# MCU.net
KiCad netlist of a schematic drawn in Altium Designer
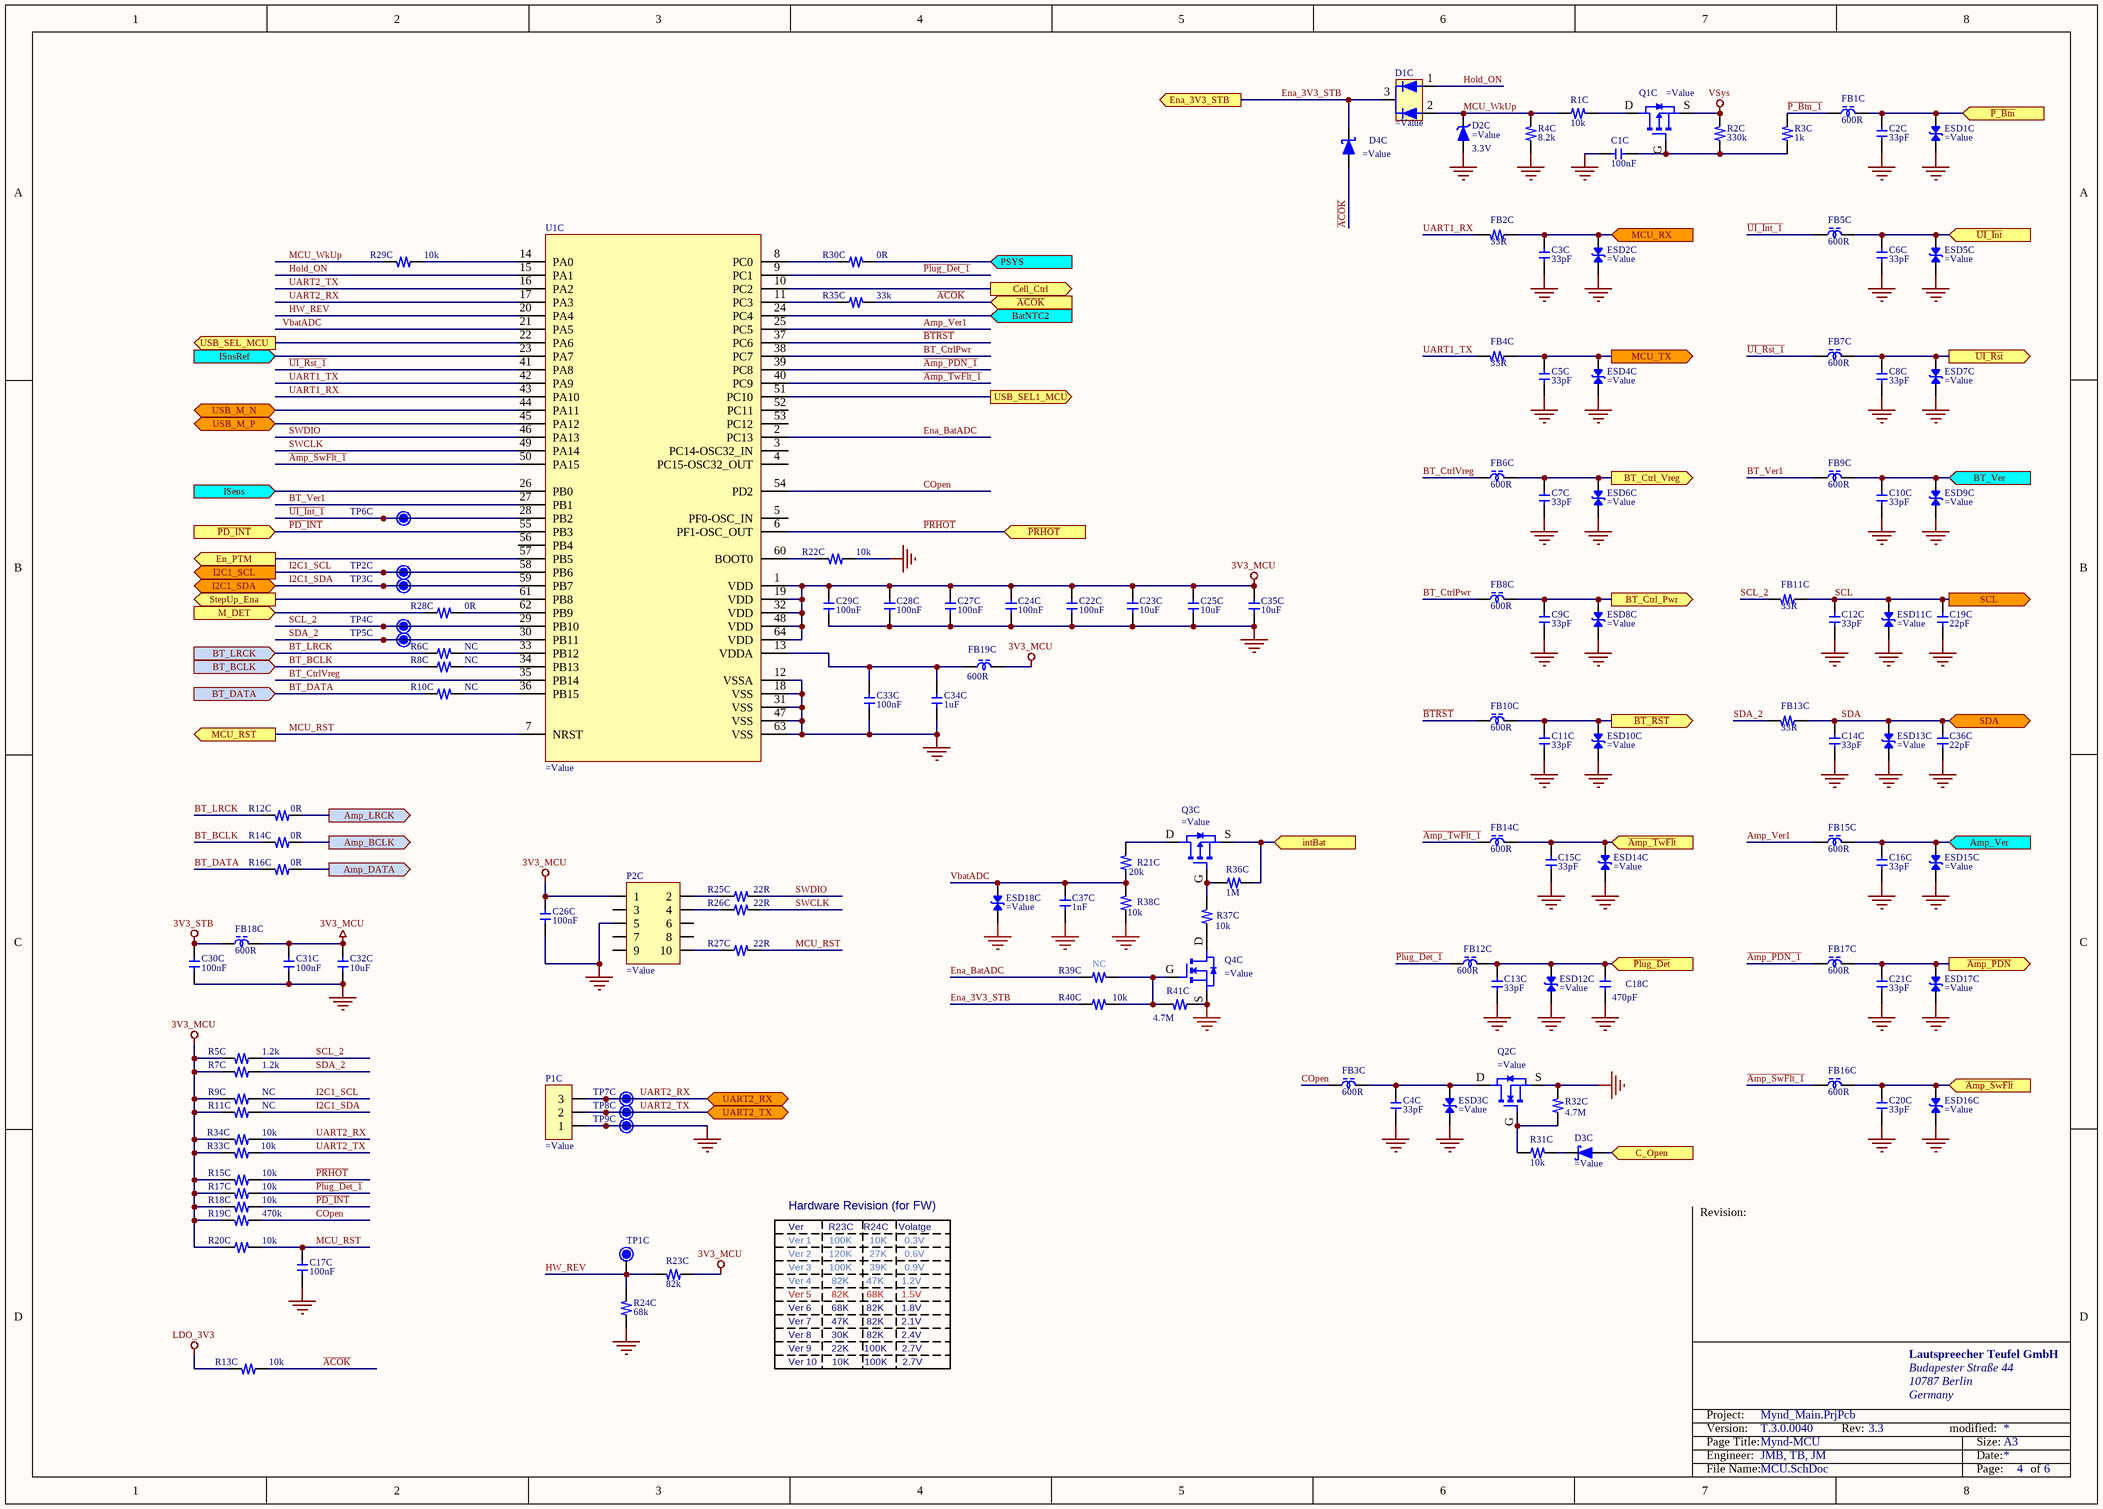
[diagram p0: MCU.SchDoc]

(export (version "E")
  (design (tool "Eeschema 10.0.6"))
  (components
    (comp (ref "C1C")
      (value "100nF")
      (footprint "C0603X100")
      (description "PSHF SMD M CAP 100nF 50V ±10% 0603 X7R")
      (fields (field (name "MANUFACTURER") "Multi Sourced") (field (name "TOLERANCE") "±10%"))
      (libsource (lib "altium-import") (part "root_0_mirrored_CAP1_"))
    )
    (comp (ref "C2C")
      (value "33pF")
      (footprint "C0603X80")
      (description "PSHF SMD M CAP 33pF 50V ±5% 0603 NPO")
      (fields (field (name "MANUFACTURER") "Multi Sourced") (field (name "TOLERANCE") "±5%"))
      (libsource (lib "altium-import") (part "root_3_mirrored_CAP1_"))
    )
    (comp (ref "C3C")
      (value "33pF")
      (footprint "C0603X80")
      (description "PSHF SMD M CAP 33pF 50V ±5% 0603 NPO")
      (fields (field (name "MANUFACTURER") "Multi Sourced") (field (name "TOLERANCE") "±5%"))
      (libsource (lib "altium-import") (part "root_3_mirrored_CAP1_"))
    )
    (comp (ref "C4C")
      (value "33pF")
      (footprint "C0603X80")
      (description "PSHF SMD M CAP 33pF 50V ±5% 0603 NPO")
      (fields (field (name "MANUFACTURER") "Multi Sourced") (field (name "TOLERANCE") "±5%"))
      (libsource (lib "altium-import") (part "root_3_mirrored_CAP1_"))
    )
    (comp (ref "C5C")
      (value "33pF")
      (footprint "C0603X80")
      (description "PSHF SMD M CAP 33pF 50V ±5% 0603 NPO")
      (fields (field (name "MANUFACTURER") "Multi Sourced") (field (name "TOLERANCE") "±5%"))
      (libsource (lib "altium-import") (part "root_3_mirrored_CAP1_"))
    )
    (comp (ref "C6C")
      (value "33pF")
      (footprint "C0603X80")
      (description "PSHF SMD M CAP 33pF 50V ±5% 0603 NPO")
      (fields (field (name "MANUFACTURER") "Multi Sourced") (field (name "TOLERANCE") "±5%"))
      (libsource (lib "altium-import") (part "root_3_mirrored_CAP1_"))
    )
    (comp (ref "C7C")
      (value "33pF")
      (footprint "C0603X80")
      (description "PSHF SMD M CAP 33pF 50V ±5% 0603 NPO")
      (fields (field (name "MANUFACTURER") "Multi Sourced") (field (name "TOLERANCE") "±5%"))
      (libsource (lib "altium-import") (part "root_3_mirrored_CAP1_"))
    )
    (comp (ref "C8C")
      (value "33pF")
      (footprint "C0603X80")
      (description "PSHF SMD M CAP 33pF 50V ±5% 0603 NPO")
      (fields (field (name "MANUFACTURER") "Multi Sourced") (field (name "TOLERANCE") "±5%"))
      (libsource (lib "altium-import") (part "root_3_mirrored_CAP1_"))
    )
    (comp (ref "C9C")
      (value "33pF")
      (footprint "C0603X80")
      (description "PSHF SMD M CAP 33pF 50V ±5% 0603 NPO")
      (fields (field (name "MANUFACTURER") "Multi Sourced") (field (name "TOLERANCE") "±5%"))
      (libsource (lib "altium-import") (part "root_3_mirrored_CAP1_"))
    )
    (comp (ref "C10C")
      (value "33pF")
      (footprint "C0603X80")
      (description "PSHF SMD M CAP 33pF 50V ±5% 0603 NPO")
      (fields (field (name "MANUFACTURER") "Multi Sourced") (field (name "TOLERANCE") "±5%"))
      (libsource (lib "altium-import") (part "root_3_mirrored_CAP1_"))
    )
    (comp (ref "C11C")
      (value "33pF")
      (footprint "C0603X80")
      (description "PSHF SMD M CAP 33pF 50V ±5% 0603 NPO")
      (fields (field (name "MANUFACTURER") "Multi Sourced") (field (name "TOLERANCE") "±5%"))
      (libsource (lib "altium-import") (part "root_3_mirrored_CAP1_"))
    )
    (comp (ref "C12C")
      (value "33pF")
      (footprint "C0603X80")
      (description "PSHF SMD M CAP 33pF 50V ±5% 0603 NPO")
      (fields (field (name "MANUFACTURER") "Multi Sourced") (field (name "TOLERANCE") "±5%"))
      (libsource (lib "altium-import") (part "root_3_mirrored_CAP1_"))
    )
    (comp (ref "C13C")
      (value "33pF")
      (footprint "C0603X80")
      (description "PSHF SMD M CAP 33pF 50V ±5% 0603 NPO")
      (fields (field (name "MANUFACTURER") "Multi Sourced") (field (name "TOLERANCE") "±5%"))
      (libsource (lib "altium-import") (part "root_3_mirrored_CAP1_"))
    )
    (comp (ref "C14C")
      (value "33pF")
      (footprint "C0603X80")
      (description "PSHF SMD M CAP 33pF 50V ±5% 0603 NPO")
      (fields (field (name "MANUFACTURER") "Multi Sourced") (field (name "TOLERANCE") "±5%"))
      (libsource (lib "altium-import") (part "root_3_mirrored_CAP1_"))
    )
    (comp (ref "C15C")
      (value "33pF")
      (footprint "C0603X80")
      (description "PSHF SMD M CAP 33pF 50V ±5% 0603 NPO")
      (fields (field (name "MANUFACTURER") "Multi Sourced") (field (name "TOLERANCE") "±5%"))
      (libsource (lib "altium-import") (part "root_3_mirrored_CAP1_"))
    )
    (comp (ref "C16C")
      (value "33pF")
      (footprint "C0603X80")
      (description "PSHF SMD M CAP 33pF 50V ±5% 0603 NPO")
      (fields (field (name "MANUFACTURER") "Multi Sourced") (field (name "TOLERANCE") "±5%"))
      (libsource (lib "altium-import") (part "root_3_mirrored_CAP1_"))
    )
    (comp (ref "C17C")
      (value "100nF")
      (footprint "C0603X100")
      (description "PSHF SMD M CAP 100nF 50V ±10% 0603 X7R")
      (fields (field (name "MANUFACTURER") "Multi Sourced") (field (name "TOLERANCE") "±10%"))
      (libsource (lib "altium-import") (part "root_3_CAP1_"))
    )
    (comp (ref "C18C")
      (value "470pF")
      (footprint "C0603X80")
      (description "GPHF SMD CAP 470pF 50V 10%")
      (fields (field (name "MANUFACTURER") "Multi Sourced") (field (name "TOLERANCE") "±10%"))
      (libsource (lib "altium-import") (part "root_3_CAP1_"))
    )
    (comp (ref "C19C")
      (value "22pF")
      (footprint "C0603X80")
      (description "GPHF SMD M CAP 22pF 50V ±5% 0603 NPO")
      (fields (field (name "MANUFACTURER") "Multi Sourced") (field (name "TOLERANCE") "±5%"))
      (libsource (lib "altium-import") (part "root_3_mirrored_CAP1_"))
    )
    (comp (ref "C20C")
      (value "33pF")
      (footprint "C0603X80")
      (description "PSHF SMD M CAP 33pF 50V ±5% 0603 NPO")
      (fields (field (name "MANUFACTURER") "Multi Sourced") (field (name "TOLERANCE") "±5%"))
      (libsource (lib "altium-import") (part "root_3_mirrored_CAP1_"))
    )
    (comp (ref "C21C")
      (value "33pF")
      (footprint "C0603X80")
      (description "PSHF SMD M CAP 33pF 50V ±5% 0603 NPO")
      (fields (field (name "MANUFACTURER") "Multi Sourced") (field (name "TOLERANCE") "±5%"))
      (libsource (lib "altium-import") (part "root_3_mirrored_CAP1_"))
    )
    (comp (ref "C22C")
      (value "100nF")
      (footprint "C0603X100")
      (description "PSHF SMD M CAP 100nF 50V ±10% 0603 X7R")
      (fields (field (name "MANUFACTURER") "Multi Sourced") (field (name "TOLERANCE") "±10%"))
      (libsource (lib "altium-import") (part "root_3_CAP1_"))
    )
    (comp (ref "C23C")
      (value "10uF")
      (footprint "C0805_145")
      (description "PSHF SMD M CAP 10uF 16V ±10% 0805 X7R")
      (fields (field (name "MANUFACTURER") "Multi Sourced") (field (name "TOLERANCE") "±10%"))
      (libsource (lib "altium-import") (part "root_3_CAP1_"))
    )
    (comp (ref "C24C")
      (value "100nF")
      (footprint "C0603X100")
      (description "PSHF SMD M CAP 100nF 50V ±10% 0603 X7R")
      (fields (field (name "MANUFACTURER") "Multi Sourced") (field (name "TOLERANCE") "±10%"))
      (libsource (lib "altium-import") (part "root_3_CAP1_"))
    )
    (comp (ref "C25C")
      (value "10uF")
      (footprint "C0805_145")
      (description "PSHF SMD M CAP 10uF 16V ±10% 0805 X7R")
      (fields (field (name "MANUFACTURER") "Multi Sourced") (field (name "TOLERANCE") "±10%"))
      (libsource (lib "altium-import") (part "root_3_CAP1_"))
    )
    (comp (ref "C26C")
      (value "100nF")
      (footprint "C0603X100")
      (description "PSHF SMD M CAP 100nF 50V ±10% 0603 X7R")
      (fields (field (name "MANUFACTURER") "Multi Sourced") (field (name "TOLERANCE") "±10%"))
      (libsource (lib "altium-import") (part "root_3_CAP1_"))
    )
    (comp (ref "C27C")
      (value "100nF")
      (footprint "C0603X100")
      (description "PSHF SMD M CAP 100nF 50V ±10% 0603 X7R")
      (fields (field (name "MANUFACTURER") "Multi Sourced") (field (name "TOLERANCE") "±10%"))
      (libsource (lib "altium-import") (part "root_3_CAP1_"))
    )
    (comp (ref "C28C")
      (value "100nF")
      (footprint "C0603X100")
      (description "PSHF SMD M CAP 100nF 50V ±10% 0603 X7R")
      (fields (field (name "MANUFACTURER") "Multi Sourced") (field (name "TOLERANCE") "±10%"))
      (libsource (lib "altium-import") (part "root_3_CAP1_"))
    )
    (comp (ref "C29C")
      (value "100nF")
      (footprint "C0603X100")
      (description "PSHF SMD M CAP 100nF 50V ±10% 0603 X7R")
      (fields (field (name "MANUFACTURER") "Multi Sourced") (field (name "TOLERANCE") "±10%"))
      (libsource (lib "altium-import") (part "root_3_CAP1_"))
    )
    (comp (ref "C30C")
      (value "100nF")
      (footprint "C0603X100")
      (description "PSHF SMD M CAP 100nF 50V ±10% 0603 X7R")
      (fields (field (name "MANUFACTURER") "Multi Sourced") (field (name "TOLERANCE") "±10%"))
      (libsource (lib "altium-import") (part "root_3_CAP1_"))
    )
    (comp (ref "C31C")
      (value "100nF")
      (footprint "C0603X100")
      (description "PSHF SMD M CAP 100nF 50V ±10% 0603 X7R")
      (fields (field (name "MANUFACTURER") "Multi Sourced") (field (name "TOLERANCE") "±10%"))
      (libsource (lib "altium-import") (part "root_3_CAP1_"))
    )
    (comp (ref "C32C")
      (value "10uF")
      (footprint "C0805_145")
      (description "PSHF SMD M CAP 10uF 16V ±10% 0805 X7R")
      (fields (field (name "MANUFACTURER") "Multi Sourced") (field (name "TOLERANCE") "±10%"))
      (libsource (lib "altium-import") (part "root_3_CAP1_"))
    )
    (comp (ref "C33C")
      (value "100nF")
      (footprint "C0603X100")
      (description "PSHF SMD M CAP 100nF 50V ±10% 0603 X7R")
      (fields (field (name "MANUFACTURER") "Multi Sourced") (field (name "TOLERANCE") "±10%"))
      (libsource (lib "altium-import") (part "root_3_CAP1_"))
    )
    (comp (ref "C34C")
      (value "1uF")
      (footprint "C0603X105")
      (description "PSHF SMD M CAP 1uF 16V ±10% 0603 X7R")
      (fields (field (name "MANUFACTURER") "Multi Sourced") (field (name "TOLERANCE") "±10%"))
      (libsource (lib "altium-import") (part "root_3_CAP1_"))
    )
    (comp (ref "C35C")
      (value "10uF")
      (footprint "C0805_145")
      (description "PSHF SMD M CAP 10uF 16V ±10% 0805 X7R")
      (fields (field (name "MANUFACTURER") "Multi Sourced") (field (name "TOLERANCE") "±10%"))
      (libsource (lib "altium-import") (part "root_1_CAP1_"))
    )
    (comp (ref "C36C")
      (value "22pF")
      (footprint "C0603X80")
      (description "GPHF SMD M CAP 22pF 50V ±5% 0603 NPO")
      (fields (field (name "MANUFACTURER") "Multi Sourced") (field (name "TOLERANCE") "±5%"))
      (libsource (lib "altium-import") (part "root_3_mirrored_CAP1_"))
    )
    (comp (ref "C37C")
      (value "1nF")
      (footprint "C0603X100")
      (description "GPHF SMD M CAP 1nF 50V ±10% 0603 X7R")
      (fields (field (name "MANUFACTURER") "Multi Sourced") (field (name "TOLERANCE") "±10%"))
      (libsource (lib "altium-import") (part "root_3_CAP1_"))
    )
    (comp (ref "D1C")
      (value "~")
      (footprint "SOT23-123")
      (description "PS SMD DIODE 3P 30V SOT-23 BAT54C CJ")
      (fields (field (name "MANUFACTURER") "[CJ]") (field (name "VOLTAGE") "30V"))
      (libsource (lib "altium-import") (part "root_3_mirrored_DIODE_SWITCHING4_"))
    )
    (comp (ref "D2C")
      (value "~")
      (footprint "SOD-123")
      (description "GP SMD ZENER 3.3V 0.5W SOD-123 CJ")
      (fields
        (field (name "MANUFACTURER") "[CJ]")
        (field (name "VOLTAGE") "3.3V")
        (field (name "PART_NUMBER") "BZT52C3V3")
      )
      (libsource (lib "altium-import") (part "root_1_mirrored_DIODE_ZENER1_"))
    )
    (comp (ref "D3C")
      (value "~")
      (footprint "SOD-323")
      (description "GP SMD DIODE 2P 30V SOD323 BAT54WS PANJIT")
      (fields (field (name "MANUFACTURER") "PANJIT") (field (name "VOLTAGE") "30V"))
      (libsource (lib "altium-import") (part "root_2_DIODE_SCHOTTKY1_"))
    )
    (comp (ref "D4C")
      (value "~")
      (footprint "SOD-323")
      (description "GP SMD DIODE 2P 30V SOD323 BAT54WS PANJIT")
      (fields (field (name "MANUFACTURER") "PANJIT") (field (name "VOLTAGE") "30V"))
      (libsource (lib "altium-import") (part "root_1_mirrored_DIODE_SCHOTTKY1_"))
    )
    (comp (ref "ESD1C")
      (value "~")
      (footprint "DFN2_100X60X50_65")
      (description "SMD TVS 2P DFN1006 BDFN2C121V")
      (fields (field (name "MANUFACTURER") "[]") (field (name "PART_NUMBER") "BDFN2C121V"))
      (libsource (lib "altium-import") (part "root_3_DIODE_BID_ESD2_"))
    )
    (comp (ref "ESD2C")
      (value "~")
      (footprint "DFN2_100X60X50_65")
      (description "GP SMD TVS 2P DFN1006-2 AU3321P1 APM")
      (fields (field (name "MANUFACTURER") "APM") (field (name "VOLTAGE") "3.3V"))
      (libsource (lib "altium-import") (part "root_1_DIODE_BID_ESD2_"))
    )
    (comp (ref "ESD3C")
      (value "~")
      (footprint "DFN2_100X60X50_65")
      (description "GP SMD TVS 2P DFN1006-2 AU3321P1 APM")
      (fields (field (name "MANUFACTURER") "APM") (field (name "VOLTAGE") "3.3V"))
      (libsource (lib "altium-import") (part "root_1_DIODE_BID_ESD2_"))
    )
    (comp (ref "ESD4C")
      (value "~")
      (footprint "DFN2_100X60X50_65")
      (description "GP SMD TVS 2P DFN1006-2 AU3321P1 APM")
      (fields (field (name "MANUFACTURER") "APM") (field (name "VOLTAGE") "3.3V"))
      (libsource (lib "altium-import") (part "root_1_DIODE_BID_ESD2_"))
    )
    (comp (ref "ESD5C")
      (value "~")
      (footprint "DFN2_100X60X50_65")
      (description "GP SMD TVS 2P DFN1006-2 AU3321P1 APM")
      (fields (field (name "MANUFACTURER") "APM") (field (name "VOLTAGE") "3.3V"))
      (libsource (lib "altium-import") (part "root_1_DIODE_BID_ESD2_"))
    )
    (comp (ref "ESD6C")
      (value "~")
      (footprint "DFN2_100X60X50_65")
      (description "GP SMD TVS 2P DFN1006-2 AU3321P1 APM")
      (fields (field (name "MANUFACTURER") "APM") (field (name "VOLTAGE") "3.3V"))
      (libsource (lib "altium-import") (part "root_1_DIODE_BID_ESD2_"))
    )
    (comp (ref "ESD7C")
      (value "~")
      (footprint "DFN2_100X60X50_65")
      (description "GP SMD TVS 2P DFN1006-2 AU3321P1 APM")
      (fields (field (name "MANUFACTURER") "APM") (field (name "VOLTAGE") "3.3V"))
      (libsource (lib "altium-import") (part "root_1_DIODE_BID_ESD2_"))
    )
    (comp (ref "ESD8C")
      (value "~")
      (footprint "DFN2_100X60X50_65")
      (description "GP SMD TVS 2P DFN1006-2 AU3321P1 APM")
      (fields (field (name "MANUFACTURER") "APM") (field (name "VOLTAGE") "3.3V"))
      (libsource (lib "altium-import") (part "root_1_DIODE_BID_ESD2_"))
    )
    (comp (ref "ESD9C")
      (value "~")
      (footprint "DFN2_100X60X50_65")
      (description "GP SMD TVS 2P DFN1006-2 AU3321P1 APM")
      (fields (field (name "MANUFACTURER") "APM") (field (name "VOLTAGE") "3.3V"))
      (libsource (lib "altium-import") (part "root_1_DIODE_BID_ESD2_"))
    )
    (comp (ref "ESD10C")
      (value "~")
      (footprint "DFN2_100X60X50_65")
      (description "GP SMD TVS 2P DFN1006-2 AU3321P1 APM")
      (fields (field (name "MANUFACTURER") "APM") (field (name "VOLTAGE") "3.3V"))
      (libsource (lib "altium-import") (part "root_1_DIODE_BID_ESD2_"))
    )
    (comp (ref "ESD11C")
      (value "~")
      (footprint "DFN2_100X60X50_65")
      (description "GP SMD TVS 2P DFN1006-2 AU3321P1 APM")
      (fields (field (name "MANUFACTURER") "APM") (field (name "VOLTAGE") "3.3V"))
      (libsource (lib "altium-import") (part "root_1_DIODE_BID_ESD2_"))
    )
    (comp (ref "ESD12C")
      (value "~")
      (footprint "DFN2_100X60X50_65")
      (description "GP SMD TVS 2P DFN1006-2 AU3321P1 APM")
      (fields (field (name "MANUFACTURER") "APM") (field (name "VOLTAGE") "3.3V"))
      (libsource (lib "altium-import") (part "root_1_DIODE_BID_ESD2_"))
    )
    (comp (ref "ESD13C")
      (value "~")
      (footprint "DFN2_100X60X50_65")
      (description "GP SMD TVS 2P DFN1006-2 AU3321P1 APM")
      (fields (field (name "MANUFACTURER") "APM") (field (name "VOLTAGE") "3.3V"))
      (libsource (lib "altium-import") (part "root_1_DIODE_BID_ESD2_"))
    )
    (comp (ref "ESD14C")
      (value "~")
      (footprint "DFN2_100X60X50_65")
      (description "GP SMD TVS 2P DFN1006-2 AU3321P1 APM")
      (fields (field (name "MANUFACTURER") "APM") (field (name "VOLTAGE") "3.3V"))
      (libsource (lib "altium-import") (part "root_1_DIODE_BID_ESD2_"))
    )
    (comp (ref "ESD15C")
      (value "~")
      (footprint "DFN2_100X60X50_65")
      (description "GP SMD TVS 2P DFN1006-2 AU3321P1 APM")
      (fields (field (name "MANUFACTURER") "APM") (field (name "VOLTAGE") "3.3V"))
      (libsource (lib "altium-import") (part "root_1_DIODE_BID_ESD2_"))
    )
    (comp (ref "ESD16C")
      (value "~")
      (footprint "DFN2_100X60X50_65")
      (description "GP SMD TVS 2P DFN1006-2 AU3321P1 APM")
      (fields (field (name "MANUFACTURER") "APM") (field (name "VOLTAGE") "3.3V"))
      (libsource (lib "altium-import") (part "root_1_DIODE_BID_ESD2_"))
    )
    (comp (ref "ESD17C")
      (value "~")
      (footprint "DFN2_100X60X50_65")
      (description "GP SMD TVS 2P DFN1006-2 AU3321P1 APM")
      (fields (field (name "MANUFACTURER") "APM") (field (name "VOLTAGE") "3.3V"))
      (libsource (lib "altium-import") (part "root_1_DIODE_BID_ESD2_"))
    )
    (comp (ref "ESD18C")
      (value "~")
      (footprint "DFN2_100X60X50_65")
      (description "GP SMD TVS 2P DFN1006-2 AU3321P1 APM")
      (fields (field (name "MANUFACTURER") "APM") (field (name "VOLTAGE") "3.3V"))
      (libsource (lib "altium-import") (part "root_1_DIODE_BID_ESD2_"))
    )
    (comp (ref "FB1C")
      (value "600R")
      (footprint "L0603")
      (description "PSHF SMD FERRITE BEAD 600OHM 25% 0603")
      (fields (field (name "MANUFACTURER") "TSA") (field (name "TOLERANCE") "1:25%"))
      (libsource (lib "altium-import") (part "root_0_Bead1_"))
    )
    (comp (ref "FB2C")
      (value "33R")
      (footprint "R0603")
      (description "GPHF SMD RES. 33OHM 1/10W 5% 0603")
      (fields (field (name "MANUFACTURER") "Multi-Sourced") (field (name "TOLERANCE") "5%"))
      (libsource (lib "altium-import") (part "root_0_RES1_"))
    )
    (comp (ref "FB3C")
      (value "600R")
      (footprint "L0603")
      (description "PSHF SMD FERRITE BEAD 600OHM 25% 0603")
      (fields (field (name "MANUFACTURER") "TSA") (field (name "TOLERANCE") "1:25%"))
      (libsource (lib "altium-import") (part "root_0_Bead1_"))
    )
    (comp (ref "FB4C")
      (value "33R")
      (footprint "R0603")
      (description "GPHF SMD RES. 33OHM 1/10W 5% 0603")
      (fields (field (name "MANUFACTURER") "Multi-Sourced") (field (name "TOLERANCE") "5%"))
      (libsource (lib "altium-import") (part "root_0_RES1_"))
    )
    (comp (ref "FB5C")
      (value "600R")
      (footprint "L0603")
      (description "PSHF SMD FERRITE BEAD 600OHM 25% 0603")
      (fields (field (name "MANUFACTURER") "TSA") (field (name "TOLERANCE") "1:25%"))
      (libsource (lib "altium-import") (part "root_0_Bead1_"))
    )
    (comp (ref "FB6C")
      (value "600R")
      (footprint "L0603")
      (description "PSHF SMD FERRITE BEAD 600OHM 25% 0603")
      (fields (field (name "MANUFACTURER") "TSA") (field (name "TOLERANCE") "1:25%"))
      (libsource (lib "altium-import") (part "root_0_Bead1_"))
    )
    (comp (ref "FB7C")
      (value "600R")
      (footprint "L0603")
      (description "PSHF SMD FERRITE BEAD 600OHM 25% 0603")
      (fields (field (name "MANUFACTURER") "TSA") (field (name "TOLERANCE") "1:25%"))
      (libsource (lib "altium-import") (part "root_0_Bead1_"))
    )
    (comp (ref "FB8C")
      (value "600R")
      (footprint "L0603")
      (description "PSHF SMD FERRITE BEAD 600OHM 25% 0603")
      (fields (field (name "MANUFACTURER") "TSA") (field (name "TOLERANCE") "1:25%"))
      (libsource (lib "altium-import") (part "root_0_Bead1_"))
    )
    (comp (ref "FB9C")
      (value "600R")
      (footprint "L0603")
      (description "PSHF SMD FERRITE BEAD 600OHM 25% 0603")
      (fields (field (name "MANUFACTURER") "TSA") (field (name "TOLERANCE") "1:25%"))
      (libsource (lib "altium-import") (part "root_0_Bead1_"))
    )
    (comp (ref "FB10C")
      (value "600R")
      (footprint "L0603")
      (description "PSHF SMD FERRITE BEAD 600OHM 25% 0603")
      (fields (field (name "MANUFACTURER") "TSA") (field (name "TOLERANCE") "1:25%"))
      (libsource (lib "altium-import") (part "root_0_Bead1_"))
    )
    (comp (ref "FB11C")
      (value "33R")
      (footprint "R0603")
      (description "GPHF SMD RES. 33OHM 1/10W 5% 0603")
      (fields (field (name "MANUFACTURER") "Multi-Sourced") (field (name "TOLERANCE") "5%"))
      (libsource (lib "altium-import") (part "root_0_RES1_"))
    )
    (comp (ref "FB12C")
      (value "600R")
      (footprint "L0603")
      (description "PSHF SMD FERRITE BEAD 600OHM 25% 0603")
      (fields (field (name "MANUFACTURER") "TSA") (field (name "TOLERANCE") "1:25%"))
      (libsource (lib "altium-import") (part "root_0_Bead1_"))
    )
    (comp (ref "FB13C")
      (value "33R")
      (footprint "R0603")
      (description "GPHF SMD RES. 33OHM 1/10W 5% 0603")
      (fields (field (name "MANUFACTURER") "Multi-Sourced") (field (name "TOLERANCE") "5%"))
      (libsource (lib "altium-import") (part "root_0_RES1_"))
    )
    (comp (ref "FB14C")
      (value "600R")
      (footprint "L0603")
      (description "PSHF SMD FERRITE BEAD 600OHM 25% 0603")
      (fields (field (name "MANUFACTURER") "TSA") (field (name "TOLERANCE") "1:25%"))
      (libsource (lib "altium-import") (part "root_0_Bead1_"))
    )
    (comp (ref "FB15C")
      (value "600R")
      (footprint "L0603")
      (description "PSHF SMD FERRITE BEAD 600OHM 25% 0603")
      (fields (field (name "MANUFACTURER") "TSA") (field (name "TOLERANCE") "1:25%"))
      (libsource (lib "altium-import") (part "root_0_Bead1_"))
    )
    (comp (ref "FB16C")
      (value "600R")
      (footprint "L0603")
      (description "PSHF SMD FERRITE BEAD 600OHM 25% 0603")
      (fields (field (name "MANUFACTURER") "TSA") (field (name "TOLERANCE") "1:25%"))
      (libsource (lib "altium-import") (part "root_0_Bead1_"))
    )
    (comp (ref "FB17C")
      (value "600R")
      (footprint "L0603")
      (description "PSHF SMD FERRITE BEAD 600OHM 25% 0603")
      (fields (field (name "MANUFACTURER") "TSA") (field (name "TOLERANCE") "1:25%"))
      (libsource (lib "altium-import") (part "root_0_Bead1_"))
    )
    (comp (ref "FB18C")
      (value "600R")
      (footprint "L0603")
      (description "PSHF SMD FERRITE BEAD 600OHM 25% 0603")
      (fields (field (name "MANUFACTURER") "TSA") (field (name "TOLERANCE") "1:25%"))
      (libsource (lib "altium-import") (part "root_0_Bead1_"))
    )
    (comp (ref "FB19C")
      (value "600R")
      (footprint "L0603")
      (description "PSHF SMD FERRITE BEAD 600OHM 25% 0603")
      (fields (field (name "MANUFACTURER") "TSA") (field (name "TOLERANCE") "1:25%"))
      (libsource (lib "altium-import") (part "root_0_Bead1_"))
    )
    (comp (ref "P1C")
      (value "~")
      (footprint "Pin_Header_SMD_S_T_254_3P")
      (description "GP HEADER PIN 3P P=2.54mm 90° GOLD")
      (fields (field (name "MANUFACTURER") "[null]") (field (name "PART_NUMBER") "3P PITCH=2.54mm"))
      (libsource (lib "altium-import") (part "root_2_mirrored_CON 3P_"))
    )
    (comp (ref "P2C")
      (value "~")
      (footprint "Pin_Header_2x5_127")
      (description "SMD BTB CONNECTOR 10P P1.27mm GOLD")
      (fields (field (name "MANUFACTURER") "MINGHENG") (field (name "PART_NUMBER") "1.27PH 2X5P H2.0 SMT"))
      (libsource (lib "altium-import") (part "root_0_CON 2X5P_"))
    )
    (comp (ref "Q1C")
      (value "~")
      (footprint "SOT23-GSD")
      (description "GS SMD FET 3P -30V SOT-23 CJ3401 CJ")
      (fields (field (name "MANUFACTURER") "[CJ]") (field (name "VOLTAGE") "-30"))
      (libsource (lib "altium-import") (part "root_1_P-MOS1_"))
    )
    (comp (ref "Q2C")
      (value "~")
      (footprint "SOT23-GSD")
      (description "GP SMD FET 3P SOT23 2N7002K CTE")
      (fields (field (name "MANUFACTURER") "CTE") (field (name "VOLTAGE") "60V"))
      (libsource (lib "altium-import") (part "root_1_N-MOS1_"))
    )
    (comp (ref "Q3C")
      (value "~")
      (footprint "SOT23-GSD")
      (description "GS SMD FET 3P -30V SOT-23 CJ3401 CJ")
      (fields (field (name "MANUFACTURER") "[CJ]") (field (name "VOLTAGE") "-30"))
      (libsource (lib "altium-import") (part "root_1_P-MOS1_"))
    )
    (comp (ref "Q4C")
      (value "~")
      (footprint "SOT23-GSD")
      (description "GP SMD FET 3P SOT23 2N7002K CTE")
      (fields (field (name "MANUFACTURER") "CTE") (field (name "VOLTAGE") "60V"))
      (libsource (lib "altium-import") (part "root_0_N-MOS1_"))
    )
    (comp (ref "R1C")
      (value "10k")
      (footprint "R0603")
      (description "PS SMD RES. 10KOHM 1/10W 1% 0603")
      (fields (field (name "TOLERANCE") "1%") (field (name "MANUFACTURER") "Multi-Sourced"))
      (libsource (lib "altium-import") (part "root_2_mirrored_RES1_"))
    )
    (comp (ref "R2C")
      (value "330k")
      (footprint "R0603")
      (description "PS SMD RES. 330KOHM 1/10W 1% 0603")
      (fields (field (name "TOLERANCE") "1%") (field (name "MANUFACTURER") "Multi-Sourced"))
      (libsource (lib "altium-import") (part "root_1_mirrored_RES1_"))
    )
    (comp (ref "R3C")
      (value "1k")
      (footprint "R0603")
      (description "PS SMD RES. 1KOHM 1/10W 1% 0603")
      (fields (field (name "TOLERANCE") "1%") (field (name "MANUFACTURER") "Multi-Sourced"))
      (libsource (lib "altium-import") (part "root_1_mirrored_RES1_"))
    )
    (comp (ref "R4C")
      (value "8.2k")
      (footprint "R0603")
      (description "PS SMD RES. 8.2KOHM 1/10W 1% 0603")
      (fields (field (name "TOLERANCE") "1%") (field (name "MANUFACTURER") "Multi-Sourced"))
      (libsource (lib "altium-import") (part "root_1_mirrored_RES1_"))
    )
    (comp (ref "R5C")
      (value "1.2k")
      (footprint "R0603")
      (description "PS SMD RES. 1.2KOHM 1/10W 1% 0603")
      (fields (field (name "TOLERANCE") "1%") (field (name "MANUFACTURER") "Multi-Sourced"))
      (libsource (lib "altium-import") (part "root_0_RES1_"))
    )
    (comp (ref "R6C")
      (value "NC")
      (footprint "R0603")
      (description "PS SMD RES. 0OHM 1/10W 5% 0603")
      (fields (field (name "TOLERANCE") "5%") (field (name "MANUFACTURER") "Multi-Sourced"))
      (libsource (lib "altium-import") (part "root_2_RES1_"))
    )
    (comp (ref "R7C")
      (value "1.2k")
      (footprint "R0603")
      (description "PS SMD RES. 1.2KOHM 1/10W 1% 0603")
      (fields (field (name "TOLERANCE") "1%") (field (name "MANUFACTURER") "Multi-Sourced"))
      (libsource (lib "altium-import") (part "root_0_RES1_"))
    )
    (comp (ref "R8C")
      (value "NC")
      (footprint "R0603")
      (description "PS SMD RES. 0OHM 1/10W 5% 0603")
      (fields (field (name "TOLERANCE") "5%") (field (name "MANUFACTURER") "Multi-Sourced"))
      (libsource (lib "altium-import") (part "root_2_RES1_"))
    )
    (comp (ref "R9C")
      (value "NC")
      (footprint "R0603")
      (description "PS SMD RES. 10KOHM 1/10W 1% 0603")
      (fields (field (name "TOLERANCE") "1%") (field (name "MANUFACTURER") "Multi-Sourced"))
      (libsource (lib "altium-import") (part "root_0_RES1_"))
    )
    (comp (ref "R10C")
      (value "NC")
      (footprint "R0603")
      (description "PS SMD RES. 0OHM 1/10W 5% 0603")
      (fields (field (name "TOLERANCE") "5%") (field (name "MANUFACTURER") "Multi-Sourced"))
      (libsource (lib "altium-import") (part "root_2_RES1_"))
    )
    (comp (ref "R11C")
      (value "NC")
      (footprint "R0603")
      (description "PS SMD RES. 10KOHM 1/10W 1% 0603")
      (fields (field (name "TOLERANCE") "1%") (field (name "MANUFACTURER") "Multi-Sourced"))
      (libsource (lib "altium-import") (part "root_0_RES1_"))
    )
    (comp (ref "R12C")
      (value "0R")
      (footprint "R0603")
      (description "PS SMD RES. 0OHM 1/10W 5% 0603")
      (fields (field (name "TOLERANCE") "1%") (field (name "MANUFACTURER") "Multi-Sourced"))
      (libsource (lib "altium-import") (part "root_0_RES1_"))
    )
    (comp (ref "R13C")
      (value "10k")
      (footprint "R0603")
      (description "PS SMD RES. 10KOHM 1/10W 1% 0603")
      (fields (field (name "TOLERANCE") "1%") (field (name "MANUFACTURER") "Multi-Sourced"))
      (libsource (lib "altium-import") (part "root_0_RES1_"))
    )
    (comp (ref "R14C")
      (value "0R")
      (footprint "R0603")
      (description "PS SMD RES. 0OHM 1/10W 5% 0603")
      (fields (field (name "TOLERANCE") "1%") (field (name "MANUFACTURER") "Multi-Sourced"))
      (libsource (lib "altium-import") (part "root_0_RES1_"))
    )
    (comp (ref "R15C")
      (value "10k")
      (footprint "R0603")
      (description "PS SMD RES. 10KOHM 1/10W 1% 0603")
      (fields (field (name "TOLERANCE") "1%") (field (name "MANUFACTURER") "Multi-Sourced"))
      (libsource (lib "altium-import") (part "root_0_RES1_"))
    )
    (comp (ref "R16C")
      (value "0R")
      (footprint "R0603")
      (description "PS SMD RES. 0OHM 1/10W 5% 0603")
      (fields (field (name "TOLERANCE") "1%") (field (name "MANUFACTURER") "Multi-Sourced"))
      (libsource (lib "altium-import") (part "root_0_RES1_"))
    )
    (comp (ref "R17C")
      (value "10k")
      (footprint "R0603")
      (description "PS SMD RES. 10KOHM 1/10W 1% 0603")
      (fields (field (name "TOLERANCE") "1%") (field (name "MANUFACTURER") "Multi-Sourced"))
      (libsource (lib "altium-import") (part "root_0_RES1_"))
    )
    (comp (ref "R18C")
      (value "10k")
      (footprint "R0603")
      (description "PS SMD RES. 10KOHM 1/10W 1% 0603")
      (fields (field (name "TOLERANCE") "1%") (field (name "MANUFACTURER") "Multi-Sourced"))
      (libsource (lib "altium-import") (part "root_0_RES1_"))
    )
    (comp (ref "R19C")
      (value "470k")
      (footprint "R0603")
      (description "PS SMD RES. 470KOHM 1/10W 1% 0603")
      (fields (field (name "TOLERANCE") "1%") (field (name "MANUFACTURER") "Multi-Sourced"))
      (libsource (lib "altium-import") (part "root_0_RES1_"))
    )
    (comp (ref "R20C")
      (value "10k")
      (footprint "R0603")
      (description "PS SMD RES. 10KOHM 1/10W 1% 0603")
      (fields (field (name "TOLERANCE") "1%") (field (name "MANUFACTURER") "Multi-Sourced"))
      (libsource (lib "altium-import") (part "root_2_RES1_"))
    )
    (comp (ref "R21C")
      (value "20k")
      (footprint "R0603")
      (description "GPHF SMD RES. 20KOHM 1/10W 1% 0603")
      (fields (field (name "TOLERANCE") "1%") (field (name "MANUFACTURER") "Multi-Sourced"))
      (libsource (lib "altium-import") (part "root_1_mirrored_RES1_"))
    )
    (comp (ref "R22C")
      (value "10k")
      (footprint "R0603")
      (description "PS SMD RES. 10KOHM 1/10W 1% 0603")
      (fields (field (name "TOLERANCE") "1%") (field (name "MANUFACTURER") "Multi-Sourced"))
      (libsource (lib "altium-import") (part "root_0_mirrored_RES1_"))
    )
    (comp (ref "R23C")
      (value "82k")
      (footprint "R0603")
      (description "GPHF SMD RES. 82KOHM 1/10W 1% 0603")
      (fields (field (name "TOLERANCE") "1%") (field (name "MANUFACTURER") "Multi-Sourced"))
      (libsource (lib "altium-import") (part "root_0_mirrored_RES1_"))
    )
    (comp (ref "R24C")
      (value "68k")
      (footprint "R0603")
      (description "GPHF SMD RES. 68KOHM 1/10W 1% 0603")
      (fields (field (name "TOLERANCE") "1%") (field (name "MANUFACTURER") "Multi-Sourced"))
      (libsource (lib "altium-import") (part "root_1_mirrored_RES1_"))
    )
    (comp (ref "R25C")
      (value "22R")
      (footprint "R0603")
      (description "PS SMD RES. 22OHM 1/10W 5% 0603")
      (fields (field (name "TOLERANCE") "1%") (field (name "MANUFACTURER") "Multi-Sourced"))
      (libsource (lib "altium-import") (part "root_2_RES1_"))
    )
    (comp (ref "R26C")
      (value "22R")
      (footprint "R0603")
      (description "PS SMD RES. 22OHM 1/10W 5% 0603")
      (fields (field (name "TOLERANCE") "1%") (field (name "MANUFACTURER") "Multi-Sourced"))
      (libsource (lib "altium-import") (part "root_2_RES1_"))
    )
    (comp (ref "R27C")
      (value "22R")
      (footprint "R0603")
      (description "PS SMD RES. 22OHM 1/10W 5% 0603")
      (fields (field (name "TOLERANCE") "1%") (field (name "MANUFACTURER") "Multi-Sourced"))
      (libsource (lib "altium-import") (part "root_2_RES1_"))
    )
    (comp (ref "R28C")
      (value "0R")
      (footprint "R0603")
      (description "PS SMD RES. 0OHM 1/10W 5% 0603")
      (fields (field (name "TOLERANCE") "5%") (field (name "MANUFACTURER") "Multi-Sourced"))
      (libsource (lib "altium-import") (part "root_2_RES1_"))
    )
    (comp (ref "R29C")
      (value "10k")
      (footprint "R0603")
      (description "PS SMD RES. 10KOHM 1/10W 1% 0603")
      (fields (field (name "TOLERANCE") "1%") (field (name "MANUFACTURER") "Multi-Sourced"))
      (libsource (lib "altium-import") (part "root_0_mirrored_RES1_"))
    )
    (comp (ref "R30C")
      (value "0R")
      (footprint "R0603")
      (description "PS SMD RES. 0OHM 1/10W 5% 0603")
      (fields (field (name "TOLERANCE") "1%") (field (name "MANUFACTURER") "Multi-Sourced"))
      (libsource (lib "altium-import") (part "root_2_RES1_"))
    )
    (comp (ref "R31C")
      (value "10k")
      (footprint "R0603")
      (description "PS SMD RES. 10KOHM 1/10W 1% 0603")
      (fields (field (name "TOLERANCE") "1%") (field (name "MANUFACTURER") "Multi-Sourced"))
      (libsource (lib "altium-import") (part "root_2_RES1_"))
    )
    (comp (ref "R32C")
      (value "4.7M")
      (footprint "R0603")
      (description "PS SMD RES. 4.7MOHM 1/10W 5% 0603")
      (fields (field (name "TOLERANCE") "5%") (field (name "MANUFACTURER") "Multi-Sourced"))
      (libsource (lib "altium-import") (part "root_1_mirrored_RES1_"))
    )
    (comp (ref "R33C")
      (value "10k")
      (footprint "R0603")
      (description "PS SMD RES. 10KOHM 1/10W 1% 0603")
      (fields (field (name "TOLERANCE") "1%") (field (name "MANUFACTURER") "Multi-Sourced"))
      (libsource (lib "altium-import") (part "root_0_RES1_"))
    )
    (comp (ref "R34C")
      (value "10k")
      (footprint "R0603")
      (description "PS SMD RES. 10KOHM 1/10W 1% 0603")
      (fields (field (name "TOLERANCE") "1%") (field (name "MANUFACTURER") "Multi-Sourced"))
      (libsource (lib "altium-import") (part "root_0_RES1_"))
    )
    (comp (ref "R35C")
      (value "33k")
      (footprint "R0603")
      (description "GPHF SMD RES. 33KOHM 1/10W 1% 0603")
      (fields (field (name "TOLERANCE") "1%") (field (name "MANUFACTURER") "Multi-Sourced"))
      (libsource (lib "altium-import") (part "root_2_RES1_"))
    )
    (comp (ref "R36C")
      (value "1M")
      (footprint "R0603")
      (description "GPHF SMD RES. 1MOHM 1/10W 1% 0603")
      (fields (field (name "TOLERANCE") "1%") (field (name "MANUFACTURER") "Multi-Sourced"))
      (libsource (lib "altium-import") (part "root_2_mirrored_RES1_"))
    )
    (comp (ref "R37C")
      (value "10k")
      (footprint "R0603")
      (description "PS SMD RES. 10KOHM 1/10W 1% 0603")
      (fields (field (name "TOLERANCE") "1%") (field (name "MANUFACTURER") "Multi-Sourced"))
      (libsource (lib "altium-import") (part "root_1_mirrored_RES1_"))
    )
    (comp (ref "R38C")
      (value "10k")
      (footprint "R0603")
      (description "PS SMD RES. 10KOHM 1/10W 1% 0603")
      (fields (field (name "TOLERANCE") "1%") (field (name "MANUFACTURER") "Multi-Sourced"))
      (libsource (lib "altium-import") (part "root_1_mirrored_RES1_"))
    )
    (comp (ref "R39C")
      (value "10k")
      (footprint "R0603")
      (description "PS SMD RES. 10KOHM 1/10W 1% 0603")
      (fields (field (name "TOLERANCE") "1%") (field (name "MANUFACTURER") "Multi-Sourced"))
      (libsource (lib "altium-import") (part "root_2_mirrored_RES1_"))
    )
    (comp (ref "R40C")
      (value "10k")
      (footprint "R0603")
      (description "PS SMD RES. 10KOHM 1/10W 1% 0603")
      (fields (field (name "TOLERANCE") "1%") (field (name "MANUFACTURER") "Multi-Sourced"))
      (libsource (lib "altium-import") (part "root_2_mirrored_RES1_"))
    )
    (comp (ref "R41C")
      (value "4.7M")
      (footprint "R0603")
      (description "PS SMD RES. 4.7MOHM 1/10W 5% 0603")
      (fields (field (name "TOLERANCE") "5%") (field (name "MANUFACTURER") "Multi-Sourced"))
      (libsource (lib "altium-import") (part "root_0_RES1_"))
    )
    (comp (ref "TP1C")
      (value "TP")
      (footprint "TP060")
      (description "Test Point")
      (libsource (lib "altium-import") (part "root_1_mirrored_TP_"))
    )
    (comp (ref "TP2C")
      (value "TP_T_60_40")
      (footprint "TP_T_60_40")
      (description "Test Point")
      (libsource (lib "altium-import") (part "root_0_TP_"))
    )
    (comp (ref "TP3C")
      (value "TP_T_60_40")
      (footprint "TP_T_60_40")
      (description "Test Point")
      (libsource (lib "altium-import") (part "root_0_TP_"))
    )
    (comp (ref "TP4C")
      (value "TP_T_60_40")
      (footprint "TP_T_60_40")
      (description "Test Point")
      (libsource (lib "altium-import") (part "root_0_TP_"))
    )
    (comp (ref "TP5C")
      (value "TP_T_60_40")
      (footprint "TP_T_60_40")
      (description "Test Point")
      (libsource (lib "altium-import") (part "root_0_TP_"))
    )
    (comp (ref "TP6C")
      (value "TP_T_60_40")
      (footprint "TP_T_60_40")
      (description "Test Point")
      (libsource (lib "altium-import") (part "root_0_TP_"))
    )
    (comp (ref "TP7C")
      (value "TP12")
      (footprint "TP120")
      (description "Test Point")
      (libsource (lib "altium-import") (part "root_2_mirrored_TP_"))
    )
    (comp (ref "TP8C")
      (value "TP12")
      (footprint "TP120")
      (description "Test Point")
      (libsource (lib "altium-import") (part "root_2_mirrored_TP_"))
    )
    (comp (ref "TP9C")
      (value "TP12")
      (footprint "TP120")
      (description "Test Point")
      (libsource (lib "altium-import") (part "root_2_mirrored_TP_"))
    )
    (comp (ref "U1C")
      (value "~")
      (footprint "LQFP64_1000X1000X160_50")
      (description "SMD IC 64P LQFP STM32F072RBT6 ST")
      (fields (field (name "MANUFACTURER") "ST") (field (name "PART_NUMBER") "STM32F072RBT6"))
      (libsource (lib "altium-import") (part "root_0_STM32F072RxTx_"))
    )
  )
  (nets
    (net (code "1") (name "/ACOK") (class "Default")
      (node (ref "D4C") (pin "A") (pinfunction "A_A") (pintype "passive"))
      (node (ref "R13C") (pin "2") (pinfunction "2_2") (pintype "passive"))
      (node (ref "R35C") (pin "1") (pinfunction "1_1") (pintype "passive"))
    )
    (net (code "2") (name "/Amp_BCLK") (class "Default")
      (node (ref "R14C") (pin "2") (pinfunction "2_2") (pintype "passive"))
    )
    (net (code "3") (name "/Amp_DATA") (class "Default")
      (node (ref "R16C") (pin "2") (pinfunction "2_2") (pintype "passive"))
    )
    (net (code "4") (name "/Amp_LRCK") (class "Default")
      (node (ref "R12C") (pin "2") (pinfunction "2_2") (pintype "passive"))
    )
    (net (code "5") (name "/Amp_PDN_1") (class "Default")
      (node (ref "FB17C") (pin "1") (pinfunction "1_1") (pintype "passive"))
      (node (ref "U1C") (pin "39") (pinfunction "PC8_39") (pintype "passive"))
    )
    (net (code "6") (name "/Amp_SwFlt_1") (class "Default")
      (node (ref "FB16C") (pin "1") (pinfunction "1_1") (pintype "passive"))
      (node (ref "U1C") (pin "50") (pinfunction "PA15_50") (pintype "passive"))
    )
    (net (code "7") (name "/Amp_TwFlt_1") (class "Default")
      (node (ref "FB14C") (pin "1") (pinfunction "1_1") (pintype "passive"))
      (node (ref "U1C") (pin "40") (pinfunction "PC9_40") (pintype "passive"))
    )
    (net (code "8") (name "/Amp_Ver") (class "Default")
      (node (ref "C16C") (pin "1") (pinfunction "1_1") (pintype "passive"))
      (node (ref "ESD15C") (pin "2") (pinfunction "2_2") (pintype "passive"))
      (node (ref "FB15C") (pin "2") (pinfunction "2_2") (pintype "passive"))
    )
    (net (code "9") (name "/Amp_Ver1") (class "Default")
      (node (ref "FB15C") (pin "1") (pinfunction "1_1") (pintype "passive"))
      (node (ref "U1C") (pin "25") (pinfunction "PC5_25") (pintype "passive"))
    )
    (net (code "10") (name "/BTRST") (class "Default")
      (node (ref "FB10C") (pin "1") (pinfunction "1_1") (pintype "passive"))
      (node (ref "U1C") (pin "37") (pinfunction "PC6_37") (pintype "passive"))
    )
    (net (code "11") (name "/BT_BCLK") (class "Default")
      (node (ref "R14C") (pin "1") (pinfunction "1_1") (pintype "passive"))
      (node (ref "R8C") (pin "2") (pinfunction "2_2") (pintype "passive"))
    )
    (net (code "12") (name "/BT_CtrlPwr") (class "Default")
      (node (ref "FB8C") (pin "1") (pinfunction "1_1") (pintype "passive"))
      (node (ref "U1C") (pin "38") (pinfunction "PC7_38") (pintype "passive"))
    )
    (net (code "13") (name "/BT_CtrlVreg") (class "Default")
      (node (ref "FB6C") (pin "1") (pinfunction "1_1") (pintype "passive"))
      (node (ref "U1C") (pin "35") (pinfunction "PB14_35") (pintype "passive"))
    )
    (net (code "14") (name "/BT_Ctrl_Pwr") (class "Default")
      (node (ref "C9C") (pin "1") (pinfunction "1_1") (pintype "passive"))
      (node (ref "ESD8C") (pin "2") (pinfunction "2_2") (pintype "passive"))
      (node (ref "FB8C") (pin "2") (pinfunction "2_2") (pintype "passive"))
    )
    (net (code "15") (name "/BT_Ctrl_Vreg") (class "Default")
      (node (ref "C7C") (pin "1") (pinfunction "1_1") (pintype "passive"))
      (node (ref "ESD6C") (pin "2") (pinfunction "2_2") (pintype "passive"))
      (node (ref "FB6C") (pin "2") (pinfunction "2_2") (pintype "passive"))
    )
    (net (code "16") (name "/BT_DATA") (class "Default")
      (node (ref "R10C") (pin "2") (pinfunction "2_2") (pintype "passive"))
      (node (ref "R16C") (pin "1") (pinfunction "1_1") (pintype "passive"))
    )
    (net (code "17") (name "/BT_LRCK") (class "Default")
      (node (ref "R12C") (pin "1") (pinfunction "1_1") (pintype "passive"))
      (node (ref "R6C") (pin "2") (pinfunction "2_2") (pintype "passive"))
    )
    (net (code "18") (name "/BT_RST") (class "Default")
      (node (ref "C11C") (pin "1") (pinfunction "1_1") (pintype "passive"))
      (node (ref "ESD10C") (pin "2") (pinfunction "2_2") (pintype "passive"))
      (node (ref "FB10C") (pin "2") (pinfunction "2_2") (pintype "passive"))
    )
    (net (code "19") (name "/BT_Ver") (class "Default")
      (node (ref "C10C") (pin "1") (pinfunction "1_1") (pintype "passive"))
      (node (ref "ESD9C") (pin "2") (pinfunction "2_2") (pintype "passive"))
      (node (ref "FB9C") (pin "2") (pinfunction "2_2") (pintype "passive"))
    )
    (net (code "20") (name "/BT_Ver1") (class "Default")
      (node (ref "FB9C") (pin "1") (pinfunction "1_1") (pintype "passive"))
      (node (ref "U1C") (pin "27") (pinfunction "PB1_27") (pintype "passive"))
    )
    (net (code "21") (name "/BatNTC2") (class "Default")
      (node (ref "U1C") (pin "24") (pinfunction "PC4_24") (pintype "passive"))
    )
    (net (code "22") (name "/COpen") (class "Default")
      (node (ref "FB3C") (pin "1") (pinfunction "1_1") (pintype "passive"))
      (node (ref "R19C") (pin "2") (pinfunction "2_2") (pintype "passive"))
      (node (ref "U1C") (pin "54") (pinfunction "PD2_54") (pintype "passive"))
    )
    (net (code "23") (name "/C_Open") (class "Default")
      (node (ref "D3C") (pin "A") (pinfunction "A_A") (pintype "passive"))
    )
    (net (code "24") (name "/Cell_Ctrl") (class "Default")
      (node (ref "U1C") (pin "10") (pinfunction "PC2_10") (pintype "passive"))
    )
    (net (code "25") (name "/En_PTM") (class "Default")
      (node (ref "U1C") (pin "57") (pinfunction "PB5_57") (pintype "passive"))
    )
    (net (code "26") (name "/Ena_3V3_STB") (class "Default")
      (node (ref "D1C") (pin "3") (pintype "passive"))
      (node (ref "D4C") (pin "K") (pinfunction "K_K") (pintype "passive"))
      (node (ref "R40C") (pin "1") (pinfunction "1_1") (pintype "passive"))
    )
    (net (code "27") (name "/Ena_BatADC") (class "Default")
      (node (ref "R39C") (pin "1") (pinfunction "1_1") (pintype "passive"))
      (node (ref "U1C") (pin "2") (pinfunction "PC13_2") (pintype "passive"))
    )
    (net (code "28") (name "/HW_REV") (class "Default")
      (node (ref "R23C") (pin "2") (pinfunction "2_2") (pintype "passive"))
      (node (ref "R24C") (pin "2") (pinfunction "2_2") (pintype "passive"))
      (node (ref "TP1C") (pin "1") (pinfunction "1_1") (pintype "passive"))
      (node (ref "U1C") (pin "20") (pinfunction "PA4_20") (pintype "passive"))
    )
    (net (code "29") (name "/Hold_ON") (class "Default")
      (node (ref "D1C") (pin "1") (pintype "passive"))
      (node (ref "U1C") (pin "15") (pinfunction "PA1_15") (pintype "passive"))
    )
    (net (code "30") (name "/I2C1_SCL") (class "Default")
      (node (ref "R9C") (pin "2") (pinfunction "2_2") (pintype "passive"))
      (node (ref "TP2C") (pin "1") (pinfunction "1_1") (pintype "passive"))
      (node (ref "U1C") (pin "58") (pinfunction "PB6_58") (pintype "passive"))
    )
    (net (code "31") (name "/I2C1_SDA") (class "Default")
      (node (ref "R11C") (pin "2") (pinfunction "2_2") (pintype "passive"))
      (node (ref "TP3C") (pin "1") (pinfunction "1_1") (pintype "passive"))
      (node (ref "U1C") (pin "59") (pinfunction "PB7_59") (pintype "passive"))
    )
    (net (code "32") (name "/ISens") (class "Default")
      (node (ref "U1C") (pin "26") (pinfunction "PB0_26") (pintype "passive"))
    )
    (net (code "33") (name "/ISnsRef") (class "Default")
      (node (ref "U1C") (pin "23") (pinfunction "PA7_23") (pintype "passive"))
    )
    (net (code "34") (name "/MCU_RST") (class "Default")
      (node (ref "C17C") (pin "1") (pinfunction "1_1") (pintype "passive"))
      (node (ref "R20C") (pin "1") (pinfunction "1_1") (pintype "passive"))
      (node (ref "R27C") (pin "1") (pinfunction "1_1") (pintype "passive"))
      (node (ref "U1C") (pin "7") (pinfunction "NRST_7") (pintype "passive"))
    )
    (net (code "35") (name "/MCU_RX") (class "Default")
      (node (ref "C3C") (pin "1") (pinfunction "1_1") (pintype "passive"))
      (node (ref "ESD2C") (pin "2") (pinfunction "2_2") (pintype "passive"))
      (node (ref "FB2C") (pin "2") (pinfunction "2_2") (pintype "passive"))
    )
    (net (code "36") (name "/MCU_TX") (class "Default")
      (node (ref "C5C") (pin "1") (pinfunction "1_1") (pintype "passive"))
      (node (ref "ESD4C") (pin "2") (pinfunction "2_2") (pintype "passive"))
      (node (ref "FB4C") (pin "2") (pinfunction "2_2") (pintype "passive"))
    )
    (net (code "37") (name "/MCU_WkUp") (class "Default")
      (node (ref "D1C") (pin "2") (pintype "passive"))
      (node (ref "D2C") (pin "K") (pinfunction "K_K") (pintype "passive"))
      (node (ref "R1C") (pin "1") (pinfunction "1_1") (pintype "passive"))
      (node (ref "R29C") (pin "2") (pinfunction "2_2") (pintype "passive"))
      (node (ref "R4C") (pin "2") (pinfunction "2_2") (pintype "passive"))
    )
    (net (code "38") (name "/M_DET") (class "Default")
      (node (ref "R28C") (pin "2") (pinfunction "2_2") (pintype "passive"))
    )
    (net (code "39") (name "/PD_INT") (class "Default")
      (node (ref "R18C") (pin "2") (pinfunction "2_2") (pintype "passive"))
      (node (ref "U1C") (pin "55") (pinfunction "PB3_55") (pintype "passive"))
    )
    (net (code "40") (name "/PRHOT") (class "Default")
      (node (ref "R15C") (pin "2") (pinfunction "2_2") (pintype "passive"))
      (node (ref "U1C") (pin "6") (pinfunction "PF1-OSC_OUT_6") (pintype "passive"))
    )
    (net (code "41") (name "/PSYS") (class "Default")
      (node (ref "R30C") (pin "1") (pinfunction "1_1") (pintype "passive"))
    )
    (net (code "42") (name "/P_Btn") (class "Default")
      (node (ref "C2C") (pin "1") (pinfunction "1_1") (pintype "passive"))
      (node (ref "ESD1C") (pin "1") (pinfunction "1_1") (pintype "passive"))
      (node (ref "FB1C") (pin "2") (pinfunction "2_2") (pintype "passive"))
    )
    (net (code "43") (name "/P_Btn_1") (class "Default")
      (node (ref "FB1C") (pin "1") (pinfunction "1_1") (pintype "passive"))
      (node (ref "R3C") (pin "2") (pinfunction "2_2") (pintype "passive"))
    )
    (net (code "44") (name "/Plug_Det") (class "Default")
      (node (ref "C13C") (pin "1") (pinfunction "1_1") (pintype "passive"))
      (node (ref "C18C") (pin "1") (pinfunction "1_1") (pintype "passive"))
      (node (ref "ESD12C") (pin "2") (pinfunction "2_2") (pintype "passive"))
      (node (ref "FB12C") (pin "2") (pinfunction "2_2") (pintype "passive"))
    )
    (net (code "45") (name "/Plug_Det_1") (class "Default")
      (node (ref "FB12C") (pin "1") (pinfunction "1_1") (pintype "passive"))
      (node (ref "R17C") (pin "2") (pinfunction "2_2") (pintype "passive"))
      (node (ref "U1C") (pin "9") (pinfunction "PC1_9") (pintype "passive"))
    )
    (net (code "46") (name "/SCL") (class "Default")
      (node (ref "C12C") (pin "1") (pinfunction "1_1") (pintype "passive"))
      (node (ref "C19C") (pin "1") (pinfunction "1_1") (pintype "passive"))
      (node (ref "ESD11C") (pin "2") (pinfunction "2_2") (pintype "passive"))
      (node (ref "FB11C") (pin "2") (pinfunction "2_2") (pintype "passive"))
    )
    (net (code "47") (name "/SCL_2") (class "Default")
      (node (ref "FB11C") (pin "1") (pinfunction "1_1") (pintype "passive"))
      (node (ref "R5C") (pin "2") (pinfunction "2_2") (pintype "passive"))
      (node (ref "TP4C") (pin "1") (pinfunction "1_1") (pintype "passive"))
      (node (ref "U1C") (pin "29") (pinfunction "PB10_29") (pintype "passive"))
    )
    (net (code "48") (name "/SDA") (class "Default")
      (node (ref "C14C") (pin "1") (pinfunction "1_1") (pintype "passive"))
      (node (ref "C36C") (pin "1") (pinfunction "1_1") (pintype "passive"))
      (node (ref "ESD13C") (pin "2") (pinfunction "2_2") (pintype "passive"))
      (node (ref "FB13C") (pin "2") (pinfunction "2_2") (pintype "passive"))
    )
    (net (code "49") (name "/SDA_2") (class "Default")
      (node (ref "FB13C") (pin "1") (pinfunction "1_1") (pintype "passive"))
      (node (ref "R7C") (pin "2") (pinfunction "2_2") (pintype "passive"))
      (node (ref "TP5C") (pin "1") (pinfunction "1_1") (pintype "passive"))
      (node (ref "U1C") (pin "30") (pinfunction "PB11_30") (pintype "passive"))
    )
    (net (code "50") (name "/SWCLK") (class "Default")
      (node (ref "R26C") (pin "1") (pinfunction "1_1") (pintype "passive"))
      (node (ref "U1C") (pin "49") (pinfunction "PA14_49") (pintype "passive"))
    )
    (net (code "51") (name "/SWDIO") (class "Default")
      (node (ref "R25C") (pin "1") (pinfunction "1_1") (pintype "passive"))
      (node (ref "U1C") (pin "46") (pinfunction "PA13_46") (pintype "passive"))
    )
    (net (code "52") (name "/StepUp_Ena") (class "Default")
      (node (ref "U1C") (pin "61") (pinfunction "PB8_61") (pintype "passive"))
    )
    (net (code "53") (name "/UART1_RX") (class "Default")
      (node (ref "FB2C") (pin "1") (pinfunction "1_1") (pintype "passive"))
      (node (ref "U1C") (pin "43") (pinfunction "PA10_43") (pintype "passive"))
    )
    (net (code "54") (name "/UART1_TX") (class "Default")
      (node (ref "FB4C") (pin "1") (pinfunction "1_1") (pintype "passive"))
      (node (ref "U1C") (pin "42") (pinfunction "PA9_42") (pintype "passive"))
    )
    (net (code "55") (name "/UART2_RX") (class "Default")
      (node (ref "P1C") (pin "3") (pinfunction "3_3") (pintype "passive"))
      (node (ref "R34C") (pin "2") (pinfunction "2_2") (pintype "passive"))
      (node (ref "TP7C") (pin "1") (pinfunction "1_1") (pintype "passive"))
      (node (ref "U1C") (pin "17") (pinfunction "PA3_17") (pintype "passive"))
    )
    (net (code "56") (name "/UART2_TX") (class "Default")
      (node (ref "P1C") (pin "2") (pinfunction "2_2") (pintype "passive"))
      (node (ref "R33C") (pin "2") (pinfunction "2_2") (pintype "passive"))
      (node (ref "TP8C") (pin "1") (pinfunction "1_1") (pintype "passive"))
      (node (ref "U1C") (pin "16") (pinfunction "PA2_16") (pintype "passive"))
    )
    (net (code "57") (name "/UI_Int") (class "Default")
      (node (ref "C6C") (pin "1") (pinfunction "1_1") (pintype "passive"))
      (node (ref "ESD5C") (pin "2") (pinfunction "2_2") (pintype "passive"))
      (node (ref "FB5C") (pin "2") (pinfunction "2_2") (pintype "passive"))
    )
    (net (code "58") (name "/UI_Int_1") (class "Default")
      (node (ref "FB5C") (pin "1") (pinfunction "1_1") (pintype "passive"))
      (node (ref "TP6C") (pin "1") (pinfunction "1_1") (pintype "passive"))
      (node (ref "U1C") (pin "28") (pinfunction "PB2_28") (pintype "passive"))
    )
    (net (code "59") (name "/UI_Rst") (class "Default")
      (node (ref "C8C") (pin "1") (pinfunction "1_1") (pintype "passive"))
      (node (ref "ESD7C") (pin "2") (pinfunction "2_2") (pintype "passive"))
      (node (ref "FB7C") (pin "2") (pinfunction "2_2") (pintype "passive"))
    )
    (net (code "60") (name "/UI_Rst_1") (class "Default")
      (node (ref "FB7C") (pin "1") (pinfunction "1_1") (pintype "passive"))
      (node (ref "U1C") (pin "41") (pinfunction "PA8_41") (pintype "passive"))
    )
    (net (code "61") (name "/USB_M_N") (class "Default")
      (node (ref "U1C") (pin "44") (pinfunction "PA11_44") (pintype "passive"))
    )
    (net (code "62") (name "/USB_M_P") (class "Default")
      (node (ref "U1C") (pin "45") (pinfunction "PA12_45") (pintype "passive"))
    )
    (net (code "63") (name "/USB_SEL1_MCU") (class "Default")
      (node (ref "U1C") (pin "51") (pinfunction "PC10_51") (pintype "passive"))
    )
    (net (code "64") (name "/USB_SEL_MCU") (class "Default")
      (node (ref "U1C") (pin "22") (pinfunction "PA6_22") (pintype "passive"))
    )
    (net (code "65") (name "/VbatADC") (class "Default")
      (node (ref "C37C") (pin "1") (pinfunction "1_1") (pintype "passive"))
      (node (ref "ESD18C") (pin "2") (pinfunction "2_2") (pintype "passive"))
      (node (ref "R21C") (pin "1") (pinfunction "1_1") (pintype "passive"))
      (node (ref "R38C") (pin "2") (pinfunction "2_2") (pintype "passive"))
      (node (ref "U1C") (pin "21") (pinfunction "PA5_21") (pintype "passive"))
    )
    (net (code "66") (name "/intBat") (class "Default")
      (node (ref "Q3C") (pin "S") (pinfunction "S_S") (pintype "passive"))
      (node (ref "R36C") (pin "2") (pinfunction "2_2") (pintype "passive"))
    )
    (net (code "67") (name "/~{Amp_PDN}") (class "Default")
      (node (ref "C21C") (pin "1") (pinfunction "1_1") (pintype "passive"))
      (node (ref "ESD17C") (pin "2") (pinfunction "2_2") (pintype "passive"))
      (node (ref "FB17C") (pin "2") (pinfunction "2_2") (pintype "passive"))
    )
    (net (code "68") (name "/~{Amp_SwFlt}") (class "Default")
      (node (ref "C20C") (pin "1") (pinfunction "1_1") (pintype "passive"))
      (node (ref "ESD16C") (pin "2") (pinfunction "2_2") (pintype "passive"))
      (node (ref "FB16C") (pin "2") (pinfunction "2_2") (pintype "passive"))
    )
    (net (code "69") (name "/~{Amp_TwFlt}") (class "Default")
      (node (ref "C15C") (pin "1") (pinfunction "1_1") (pintype "passive"))
      (node (ref "ESD14C") (pin "2") (pinfunction "2_2") (pintype "passive"))
      (node (ref "FB14C") (pin "2") (pinfunction "2_2") (pintype "passive"))
    )
    (net (code "70") (name "3V3_MCU") (class "Default")
      (node (ref "C22C") (pin "1") (pinfunction "1_1") (pintype "passive"))
      (node (ref "C23C") (pin "1") (pinfunction "1_1") (pintype "passive"))
      (node (ref "C24C") (pin "1") (pinfunction "1_1") (pintype "passive"))
      (node (ref "C25C") (pin "1") (pinfunction "1_1") (pintype "passive"))
      (node (ref "C26C") (pin "1") (pinfunction "1_1") (pintype "passive"))
      (node (ref "C27C") (pin "1") (pinfunction "1_1") (pintype "passive"))
      (node (ref "C28C") (pin "1") (pinfunction "1_1") (pintype "passive"))
      (node (ref "C29C") (pin "1") (pinfunction "1_1") (pintype "passive"))
      (node (ref "C31C") (pin "1") (pinfunction "1_1") (pintype "passive"))
      (node (ref "C32C") (pin "1") (pinfunction "1_1") (pintype "passive"))
      (node (ref "C35C") (pin "2") (pinfunction "2_2") (pintype "passive"))
      (node (ref "FB18C") (pin "2") (pinfunction "2_2") (pintype "passive"))
      (node (ref "FB19C") (pin "2") (pinfunction "2_2") (pintype "passive"))
      (node (ref "P2C") (pin "1") (pinfunction "1_1") (pintype "passive"))
      (node (ref "R11C") (pin "1") (pinfunction "1_1") (pintype "passive"))
      (node (ref "R15C") (pin "1") (pinfunction "1_1") (pintype "passive"))
      (node (ref "R17C") (pin "1") (pinfunction "1_1") (pintype "passive"))
      (node (ref "R18C") (pin "1") (pinfunction "1_1") (pintype "passive"))
      (node (ref "R19C") (pin "1") (pinfunction "1_1") (pintype "passive"))
      (node (ref "R20C") (pin "2") (pinfunction "2_2") (pintype "passive"))
      (node (ref "R23C") (pin "1") (pinfunction "1_1") (pintype "passive"))
      (node (ref "R33C") (pin "1") (pinfunction "1_1") (pintype "passive"))
      (node (ref "R34C") (pin "1") (pinfunction "1_1") (pintype "passive"))
      (node (ref "R5C") (pin "1") (pinfunction "1_1") (pintype "passive"))
      (node (ref "R7C") (pin "1") (pinfunction "1_1") (pintype "passive"))
      (node (ref "R9C") (pin "1") (pinfunction "1_1") (pintype "passive"))
      (node (ref "U1C") (pin "1") (pinfunction "VDD_1") (pintype "passive"))
      (node (ref "U1C") (pin "19") (pinfunction "VDD_19") (pintype "passive"))
      (node (ref "U1C") (pin "32") (pinfunction "VDD_32") (pintype "passive"))
      (node (ref "U1C") (pin "48") (pinfunction "VDD_48") (pintype "passive"))
      (node (ref "U1C") (pin "64") (pinfunction "VDD_64") (pintype "passive"))
    )
    (net (code "71") (name "3V3_STB") (class "Default")
      (node (ref "C30C") (pin "1") (pinfunction "1_1") (pintype "passive"))
      (node (ref "FB18C") (pin "1") (pinfunction "1_1") (pintype "passive"))
    )
    (net (code "72") (name "GND") (class "Default")
      (node (ref "C10C") (pin "2") (pinfunction "2_2") (pintype "passive"))
      (node (ref "C11C") (pin "2") (pinfunction "2_2") (pintype "passive"))
      (node (ref "C12C") (pin "2") (pinfunction "2_2") (pintype "passive"))
      (node (ref "C13C") (pin "2") (pinfunction "2_2") (pintype "passive"))
      (node (ref "C14C") (pin "2") (pinfunction "2_2") (pintype "passive"))
      (node (ref "C15C") (pin "2") (pinfunction "2_2") (pintype "passive"))
      (node (ref "C16C") (pin "2") (pinfunction "2_2") (pintype "passive"))
      (node (ref "C17C") (pin "2") (pinfunction "2_2") (pintype "passive"))
      (node (ref "C18C") (pin "2") (pinfunction "2_2") (pintype "passive"))
      (node (ref "C19C") (pin "2") (pinfunction "2_2") (pintype "passive"))
      (node (ref "C1C") (pin "2") (pinfunction "2_2") (pintype "passive"))
      (node (ref "C20C") (pin "2") (pinfunction "2_2") (pintype "passive"))
      (node (ref "C21C") (pin "2") (pinfunction "2_2") (pintype "passive"))
      (node (ref "C22C") (pin "2") (pinfunction "2_2") (pintype "passive"))
      (node (ref "C23C") (pin "2") (pinfunction "2_2") (pintype "passive"))
      (node (ref "C24C") (pin "2") (pinfunction "2_2") (pintype "passive"))
      (node (ref "C25C") (pin "2") (pinfunction "2_2") (pintype "passive"))
      (node (ref "C26C") (pin "2") (pinfunction "2_2") (pintype "passive"))
      (node (ref "C27C") (pin "2") (pinfunction "2_2") (pintype "passive"))
      (node (ref "C28C") (pin "2") (pinfunction "2_2") (pintype "passive"))
      (node (ref "C29C") (pin "2") (pinfunction "2_2") (pintype "passive"))
      (node (ref "C2C") (pin "2") (pinfunction "2_2") (pintype "passive"))
      (node (ref "C30C") (pin "2") (pinfunction "2_2") (pintype "passive"))
      (node (ref "C31C") (pin "2") (pinfunction "2_2") (pintype "passive"))
      (node (ref "C32C") (pin "2") (pinfunction "2_2") (pintype "passive"))
      (node (ref "C33C") (pin "2") (pinfunction "2_2") (pintype "passive"))
      (node (ref "C34C") (pin "2") (pinfunction "2_2") (pintype "passive"))
      (node (ref "C35C") (pin "1") (pinfunction "1_1") (pintype "passive"))
      (node (ref "C36C") (pin "2") (pinfunction "2_2") (pintype "passive"))
      (node (ref "C37C") (pin "2") (pinfunction "2_2") (pintype "passive"))
      (node (ref "C3C") (pin "2") (pinfunction "2_2") (pintype "passive"))
      (node (ref "C4C") (pin "2") (pinfunction "2_2") (pintype "passive"))
      (node (ref "C5C") (pin "2") (pinfunction "2_2") (pintype "passive"))
      (node (ref "C6C") (pin "2") (pinfunction "2_2") (pintype "passive"))
      (node (ref "C7C") (pin "2") (pinfunction "2_2") (pintype "passive"))
      (node (ref "C8C") (pin "2") (pinfunction "2_2") (pintype "passive"))
      (node (ref "C9C") (pin "2") (pinfunction "2_2") (pintype "passive"))
      (node (ref "D2C") (pin "A") (pinfunction "A_A") (pintype "passive"))
      (node (ref "ESD10C") (pin "1") (pinfunction "1_1") (pintype "passive"))
      (node (ref "ESD11C") (pin "1") (pinfunction "1_1") (pintype "passive"))
      (node (ref "ESD12C") (pin "1") (pinfunction "1_1") (pintype "passive"))
      (node (ref "ESD13C") (pin "1") (pinfunction "1_1") (pintype "passive"))
      (node (ref "ESD14C") (pin "1") (pinfunction "1_1") (pintype "passive"))
      (node (ref "ESD15C") (pin "1") (pinfunction "1_1") (pintype "passive"))
      (node (ref "ESD16C") (pin "1") (pinfunction "1_1") (pintype "passive"))
      (node (ref "ESD17C") (pin "1") (pinfunction "1_1") (pintype "passive"))
      (node (ref "ESD18C") (pin "1") (pinfunction "1_1") (pintype "passive"))
      (node (ref "ESD1C") (pin "2") (pinfunction "2_2") (pintype "passive"))
      (node (ref "ESD2C") (pin "1") (pinfunction "1_1") (pintype "passive"))
      (node (ref "ESD3C") (pin "1") (pinfunction "1_1") (pintype "passive"))
      (node (ref "ESD4C") (pin "1") (pinfunction "1_1") (pintype "passive"))
      (node (ref "ESD5C") (pin "1") (pinfunction "1_1") (pintype "passive"))
      (node (ref "ESD6C") (pin "1") (pinfunction "1_1") (pintype "passive"))
      (node (ref "ESD7C") (pin "1") (pinfunction "1_1") (pintype "passive"))
      (node (ref "ESD8C") (pin "1") (pinfunction "1_1") (pintype "passive"))
      (node (ref "ESD9C") (pin "1") (pinfunction "1_1") (pintype "passive"))
      (node (ref "P1C") (pin "1") (pinfunction "1_1") (pintype "passive"))
      (node (ref "P2C") (pin "5") (pinfunction "5_5") (pintype "passive"))
      (node (ref "Q2C") (pin "S") (pinfunction "S_S") (pintype "passive"))
      (node (ref "Q4C") (pin "S") (pinfunction "S_S") (pintype "passive"))
      (node (ref "R22C") (pin "1") (pinfunction "1_1") (pintype "passive"))
      (node (ref "R24C") (pin "1") (pinfunction "1_1") (pintype "passive"))
      (node (ref "R32C") (pin "2") (pinfunction "2_2") (pintype "passive"))
      (node (ref "R38C") (pin "1") (pinfunction "1_1") (pintype "passive"))
      (node (ref "R41C") (pin "2") (pinfunction "2_2") (pintype "passive"))
      (node (ref "R4C") (pin "1") (pinfunction "1_1") (pintype "passive"))
      (node (ref "TP9C") (pin "1") (pinfunction "1_1") (pintype "passive"))
      (node (ref "U1C") (pin "12") (pinfunction "VSSA_12") (pintype "passive"))
      (node (ref "U1C") (pin "18") (pinfunction "VSS_18") (pintype "passive"))
      (node (ref "U1C") (pin "31") (pinfunction "VSS_31") (pintype "passive"))
      (node (ref "U1C") (pin "47") (pinfunction "VSS_47") (pintype "passive"))
      (node (ref "U1C") (pin "63") (pinfunction "VSS_63") (pintype "passive"))
    )
    (net (code "73") (name "LDO_3V3") (class "Default")
      (node (ref "R13C") (pin "1") (pinfunction "1_1") (pintype "passive"))
    )
    (net (code "74") (name "Net-(C1C-Pad1)") (class "Default")
      (node (ref "C1C") (pin "1") (pinfunction "1_1") (pintype "passive"))
      (node (ref "Q1C") (pin "G") (pinfunction "G_G") (pintype "passive"))
      (node (ref "R2C") (pin "1") (pinfunction "1_1") (pintype "passive"))
      (node (ref "R3C") (pin "1") (pinfunction "1_1") (pintype "passive"))
    )
    (net (code "75") (name "Net-(C4C-Pad1)") (class "Default")
      (node (ref "C4C") (pin "1") (pinfunction "1_1") (pintype "passive"))
      (node (ref "ESD3C") (pin "2") (pinfunction "2_2") (pintype "passive"))
      (node (ref "FB3C") (pin "2") (pinfunction "2_2") (pintype "passive"))
      (node (ref "Q2C") (pin "D") (pinfunction "D_D") (pintype "passive"))
    )
    (net (code "76") (name "Net-(D3C-PadK)") (class "Default")
      (node (ref "D3C") (pin "K") (pinfunction "K_K") (pintype "passive"))
      (node (ref "R31C") (pin "1") (pinfunction "1_1") (pintype "passive"))
    )
    (net (code "77") (name "Net-(P2C-Pad2)") (class "Default")
      (node (ref "P2C") (pin "2") (pinfunction "2_2") (pintype "passive"))
      (node (ref "R25C") (pin "2") (pinfunction "2_2") (pintype "passive"))
    )
    (net (code "78") (name "Net-(P2C-Pad4)") (class "Default")
      (node (ref "P2C") (pin "4") (pinfunction "4_4") (pintype "passive"))
      (node (ref "R26C") (pin "2") (pinfunction "2_2") (pintype "passive"))
    )
    (net (code "79") (name "Net-(P2C-Pad10)") (class "Default")
      (node (ref "P2C") (pin "10") (pinfunction "10_10") (pintype "passive"))
      (node (ref "R27C") (pin "2") (pinfunction "2_2") (pintype "passive"))
    )
    (net (code "80") (name "Net-(Q1C-PadD)") (class "Default")
      (node (ref "Q1C") (pin "D") (pinfunction "D_D") (pintype "passive"))
      (node (ref "R1C") (pin "2") (pinfunction "2_2") (pintype "passive"))
    )
    (net (code "81") (name "Net-(Q2C-PadG)") (class "Default")
      (node (ref "Q2C") (pin "G") (pinfunction "G_G") (pintype "passive"))
      (node (ref "R31C") (pin "2") (pinfunction "2_2") (pintype "passive"))
      (node (ref "R32C") (pin "1") (pinfunction "1_1") (pintype "passive"))
    )
    (net (code "82") (name "Net-(Q3C-PadD)") (class "Default")
      (node (ref "Q3C") (pin "D") (pinfunction "D_D") (pintype "passive"))
      (node (ref "R21C") (pin "2") (pinfunction "2_2") (pintype "passive"))
    )
    (net (code "83") (name "Net-(Q3C-PadG)") (class "Default")
      (node (ref "Q3C") (pin "G") (pinfunction "G_G") (pintype "passive"))
      (node (ref "R36C") (pin "1") (pinfunction "1_1") (pintype "passive"))
      (node (ref "R37C") (pin "2") (pinfunction "2_2") (pintype "passive"))
    )
    (net (code "84") (name "Net-(Q4C-PadD)") (class "Default")
      (node (ref "Q4C") (pin "D") (pinfunction "D_D") (pintype "passive"))
      (node (ref "R37C") (pin "1") (pinfunction "1_1") (pintype "passive"))
    )
    (net (code "85") (name "Net-(Q4C-PadG)") (class "Default")
      (node (ref "Q4C") (pin "G") (pinfunction "G_G") (pintype "passive"))
      (node (ref "R39C") (pin "2") (pinfunction "2_2") (pintype "passive"))
      (node (ref "R40C") (pin "2") (pinfunction "2_2") (pintype "passive"))
      (node (ref "R41C") (pin "1") (pinfunction "1_1") (pintype "passive"))
    )
    (net (code "86") (name "Net-(U1C-BOOT0)") (class "Default")
      (node (ref "R22C") (pin "2") (pinfunction "2_2") (pintype "passive"))
      (node (ref "U1C") (pin "60") (pinfunction "BOOT0_60") (pintype "passive"))
    )
    (net (code "87") (name "Net-(U1C-PA0)") (class "Default")
      (node (ref "R29C") (pin "1") (pinfunction "1_1") (pintype "passive"))
      (node (ref "U1C") (pin "14") (pinfunction "PA0_14") (pintype "passive"))
    )
    (net (code "88") (name "Net-(U1C-PB9)") (class "Default")
      (node (ref "R28C") (pin "1") (pinfunction "1_1") (pintype "passive"))
      (node (ref "U1C") (pin "62") (pinfunction "PB9_62") (pintype "passive"))
    )
    (net (code "89") (name "Net-(U1C-PB12)") (class "Default")
      (node (ref "R6C") (pin "1") (pinfunction "1_1") (pintype "passive"))
      (node (ref "U1C") (pin "33") (pinfunction "PB12_33") (pintype "passive"))
    )
    (net (code "90") (name "Net-(U1C-PB13)") (class "Default")
      (node (ref "R8C") (pin "1") (pinfunction "1_1") (pintype "passive"))
      (node (ref "U1C") (pin "34") (pinfunction "PB13_34") (pintype "passive"))
    )
    (net (code "91") (name "Net-(U1C-PB15)") (class "Default")
      (node (ref "R10C") (pin "1") (pinfunction "1_1") (pintype "passive"))
      (node (ref "U1C") (pin "36") (pinfunction "PB15_36") (pintype "passive"))
    )
    (net (code "92") (name "Net-(U1C-PC0)") (class "Default")
      (node (ref "R30C") (pin "2") (pinfunction "2_2") (pintype "passive"))
      (node (ref "U1C") (pin "8") (pinfunction "PC0_8") (pintype "passive"))
    )
    (net (code "93") (name "Net-(U1C-PC3)") (class "Default")
      (node (ref "R35C") (pin "2") (pinfunction "2_2") (pintype "passive"))
      (node (ref "U1C") (pin "11") (pinfunction "PC3_11") (pintype "passive"))
    )
    (net (code "94") (name "Net-(U1C-VDDA)") (class "Default")
      (node (ref "C33C") (pin "1") (pinfunction "1_1") (pintype "passive"))
      (node (ref "C34C") (pin "1") (pinfunction "1_1") (pintype "passive"))
      (node (ref "FB19C") (pin "1") (pinfunction "1_1") (pintype "passive"))
      (node (ref "U1C") (pin "13") (pinfunction "VDDA_13") (pintype "passive"))
    )
    (net (code "95") (name "VSys") (class "Default")
      (node (ref "Q1C") (pin "S") (pinfunction "S_S") (pintype "passive"))
      (node (ref "R2C") (pin "2") (pinfunction "2_2") (pintype "passive"))
    )
    (net (code "96") (name "unconnected-(P2C-Pad3)") (class "Default")
      (node (ref "P2C") (pin "3") (pinfunction "3_3") (pintype "passive"))
    )
    (net (code "97") (name "unconnected-(P2C-Pad6)") (class "Default")
      (node (ref "P2C") (pin "6") (pinfunction "6_6") (pintype "passive"))
    )
    (net (code "98") (name "unconnected-(P2C-Pad7)") (class "Default")
      (node (ref "P2C") (pin "7") (pinfunction "7_7") (pintype "passive"))
    )
    (net (code "99") (name "unconnected-(P2C-Pad8)") (class "Default")
      (node (ref "P2C") (pin "8") (pinfunction "8_8") (pintype "passive"))
    )
    (net (code "100") (name "unconnected-(P2C-Pad9)") (class "Default")
      (node (ref "P2C") (pin "9") (pinfunction "9_9") (pintype "passive"))
    )
    (net (code "101") (name "unconnected-(U1C-PB4-Pad56)") (class "Default")
      (node (ref "U1C") (pin "56") (pinfunction "PB4_56") (pintype "passive"))
    )
    (net (code "102") (name "unconnected-(U1C-PC11-Pad52)") (class "Default")
      (node (ref "U1C") (pin "52") (pinfunction "PC11_52") (pintype "passive"))
    )
    (net (code "103") (name "unconnected-(U1C-PC12-Pad53)") (class "Default")
      (node (ref "U1C") (pin "53") (pinfunction "PC12_53") (pintype "passive"))
    )
    (net (code "104") (name "unconnected-(U1C-PC14-OSC32_IN-Pad3)") (class "Default")
      (node (ref "U1C") (pin "3") (pinfunction "PC14-OSC32_IN_3") (pintype "passive"))
    )
    (net (code "105") (name "unconnected-(U1C-PC15-OSC32_OUT-Pad4)") (class "Default")
      (node (ref "U1C") (pin "4") (pinfunction "PC15-OSC32_OUT_4") (pintype "passive"))
    )
    (net (code "106") (name "unconnected-(U1C-PF0-OSC_IN-Pad5)") (class "Default")
      (node (ref "U1C") (pin "5") (pinfunction "PF0-OSC_IN_5") (pintype "passive"))
    )
  )
)
